# Deck.net
KiCad netlist of a schematic drawn in Altium Designer
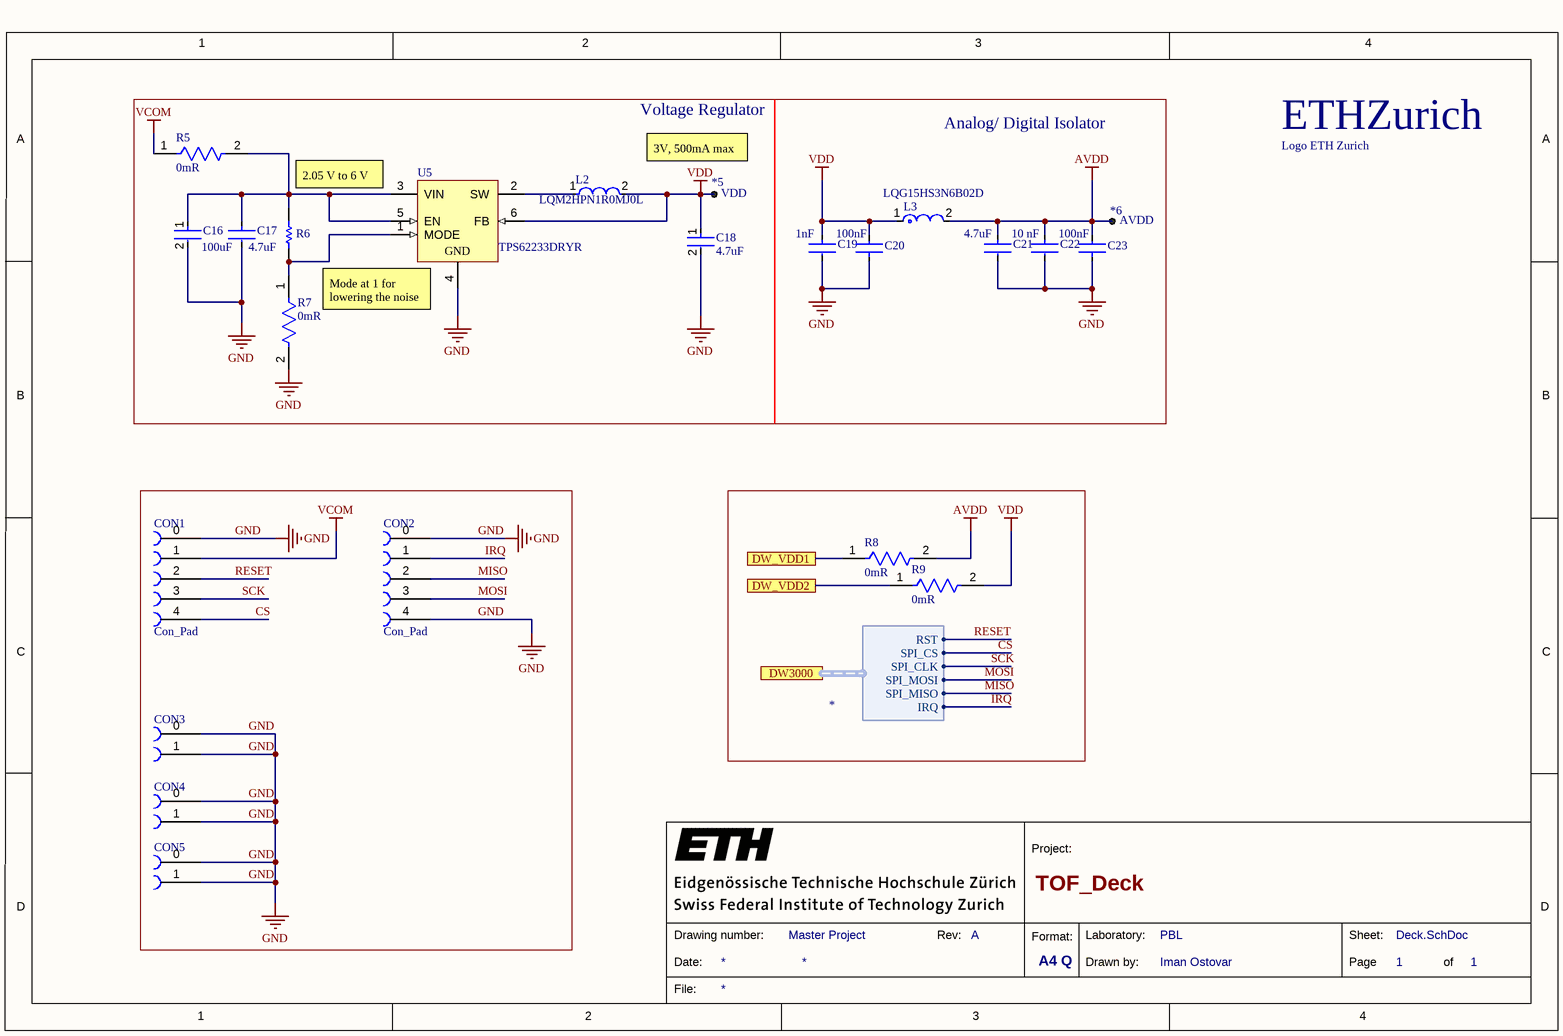
[diagram p0: Deck.SchDoc]

(export (version "E")
  (design (tool "Eeschema 10.0.6"))
  (components
    (comp (ref "*5")
      (value "VDD")
      (footprint "Pad-1mm")
      (description "1mm SMT Test Pad")
      (libsource (lib "ETHZ Vault") (part "Test Pad"))
    )
    (comp (ref "*6")
      (value "AVDD")
      (footprint "Pad-1mm")
      (description "1mm SMT Test Pad")
      (libsource (lib "ETHZ Vault") (part "Test Pad"))
    )
    (comp (ref "A1")
      (value "Logo ETH Zurich")
      (footprint "eth-zurich_3mm")
      (libsource (lib "ETHZ Vault") (part "Logo ETH Zurich"))
    )
    (comp (ref "C16")
      (value "GRM21BR60J107ME15L")
      (footprint "FP-GRM21B-0_2-e0_2_0_7-IPC_A")
      (description "Chip Multilayer Ceramic Capacitors for General Purpose, 0805, 100uF, X5R, 15%, 20%, 6.3V")
      (fields (field (name "TOLERANCE") "20%") (field (name "CAPACITANCE") "100uF"))
      (libsource (lib "Altium Content Vault") (part "b4654b650e69147ec39a6b967a45e02"))
    )
    (comp (ref "C17")
      (value "GRM155R60J475ME47D")
      (footprint "FP-GRM155-0_1-IPC_B")
      (description "Chip Multilayer Ceramic Capacitors for General Purpose, 0402, 4.7uF, X5R, 15%, 20%, 6.3V")
      (fields
        (field (name "VOLTAGE") "6.3V")
        (field (name "CAPACITANCE") "4.7uF")
        (field (name "TOLERANCE") "20%")
      )
      (libsource (lib "") (part "11868f565c42a9108669ba33697ecf6_1"))
    )
    (comp (ref "C18")
      (value "GRM155R60J475ME47D")
      (footprint "FP-GRM155-0_1-IPC_B")
      (description "Chip Multilayer Ceramic Capacitors for General Purpose, 0402, 4.7uF, X5R, 15%, 20%, 6.3V")
      (fields
        (field (name "VOLTAGE") "6.3V")
        (field (name "CAPACITANCE") "4.7uF")
        (field (name "TOLERANCE") "20%")
      )
      (libsource (lib "Altium Content Vault") (part "11868f565c42a9108669ba33697ecf6"))
    )
    (comp (ref "C19")
      (value "GRM1555C1H102JA01D")
      (footprint "FP-GRM155-0_05-IPC_B")
      (description "Chip Multilayer Ceramic Capacitors for General Purpose, 0402, 1000pF, C0G, 30ppm/°C, 5%, 50V")
      (fields
        (field (name "TOLERANCE") "5%")
        (field (name "VOLTAGE") "50V")
        (field (name "CAPACITANCE") "1nF")
      )
      (libsource (lib "Altium Content Vault") (part "02cd4be3c70576c341d710602a673aa"))
    )
    (comp (ref "C20")
      (value "GRM155R71E104ME14D")
      (footprint "FP-GRM155-0_05-IPC_B")
      (description "Chip Multilayer Ceramic Capacitors for General Purpose, 0402, 0.10uF, X7R, 15%, 20%, 25V")
      (fields (field (name "TOLERANCE") "20%") (field (name "CAPACITANCE") "100nF"))
      (libsource (lib "Altium Content Vault") (part "02cd4be3c70576c341d710602a673aa"))
    )
    (comp (ref "C21")
      (value "GRM155R60J475ME47D")
      (footprint "FP-GRM155-0_1-IPC_B")
      (description "Chip Multilayer Ceramic Capacitors for General Purpose, 0402, 4.7uF, X5R, 15%, 20%, 6.3V")
      (fields
        (field (name "VOLTAGE") "6.3V")
        (field (name "CAPACITANCE") "4.7uF")
        (field (name "TOLERANCE") "20%")
      )
      (libsource (lib "") (part "11868f565c42a9108669ba33697ecf6_1"))
    )
    (comp (ref "C22")
      (value "CC0402KRX7R7BB103")
      (footprint "FP-CC0402-MFG")
      (description "CAP CER 10000PF 16V X7R 0402")
      (fields
        (field (name "CAPACITANCE") "10 nF")
        (field (name "TOLERANCE") "0.1")
        (field (name "MANUFACTURER") "YAGEO")
      )
      (libsource (lib "") (part "11868f565c42a9108669ba33697ecf6_1"))
    )
    (comp (ref "C23")
      (value "GRM155R71E104ME14D")
      (footprint "FP-GRM155-0_05-IPC_B")
      (description "Chip Multilayer Ceramic Capacitors for General Purpose, 0402, 0.10uF, X7R, 15%, 20%, 25V")
      (fields (field (name "TOLERANCE") "20%") (field (name "CAPACITANCE") "100nF"))
      (libsource (lib "Altium Content Vault") (part "02cd4be3c70576c341d710602a673aa"))
    )
    (comp (ref "CON1")
      (value "Con_Pad")
      (footprint "PcbLib2:Cons_Pad")
      (libsource (lib "Schlib2") (part "Con_Pad"))
    )
    (comp (ref "CON2")
      (value "Con_Pad")
      (footprint "PcbLib2:Cons_Pad")
      (libsource (lib "Schlib2") (part "Con_Pad"))
    )
    (comp (ref "CON3")
      (value "Con_Pad_GND")
      (footprint "PcbLib3:PCBComponent_1")
      (libsource (lib "Schlib3") (part "Con_Pad_GND"))
    )
    (comp (ref "CON4")
      (value "Con_Pad_GND")
      (footprint "PcbLib3:PCBComponent_1")
      (libsource (lib "Schlib3") (part "Con_Pad_GND"))
    )
    (comp (ref "CON5")
      (value "Con_Pad_GND")
      (footprint "PcbLib3:PCBComponent_1")
      (libsource (lib "Schlib3") (part "Con_Pad_GND"))
    )
    (comp (ref "L2")
      (value "LQM2HPN1R0MJ0L")
      (footprint "FP-LQM2HPN_J0-IPC_B")
      (description "FIXED IND 1UH 1.5A 90 MOHM SMD")
      (fields (field (name "TOLERANCE") "20%"))
      (libsource (lib "Altium Content Vault") (part "725321dda6339637d4d059423bc1c3c"))
    )
    (comp (ref "L3")
      (value "LQG15HS3N6B02D")
      (footprint "FP-LQG15HH_02-IPC_A")
      (description "Multilayer type RF Inductor 3.6nH ±0.1nH 0.14Ω 750mA 0402")
      (libsource (lib "Altium Content Vault") (part "4cc4b267dca4c8e51f7102f422741d8"))
    )
    (comp (ref "R5")
      (value "CRCW04020000Z0ED")
      (footprint "FP-CRCW0402-e3-IPC_C")
      (description "RES Thick Film, 0Ω, 0.063W, 0402")
      (fields (field (name "TOLERANCE") "5%") (field (name "RESISTANCE") "0mR"))
      (libsource (lib "Altium Content Vault") (part "1029c3af85768c4190bb7ad29bc67b5"))
    )
    (comp (ref "R6")
      (value "CPF0402B47K5E1")
      (footprint "RESC1005X35X20LL05T10")
      (description "47.5k, CPF0402B47K5E1")
      (fields (field (name "MANUFACTURER") "TE Connectivity / AMP"))
      (libsource (lib "Altium Content Vault") (part "RES"))
    )
    (comp (ref "R7")
      (value "CRCW04020000Z0ED")
      (footprint "FP-CRCW0402-e3-IPC_C")
      (description "RES Thick Film, 0Ω, 0.063W, 0402")
      (fields (field (name "TOLERANCE") "5%") (field (name "RESISTANCE") "0mR"))
      (libsource (lib "Altium Content Vault") (part "1029c3af85768c4190bb7ad29bc67b5"))
    )
    (comp (ref "R8")
      (value "CRCW04020000Z0ED")
      (footprint "FP-CRCW0402-e3-IPC_C")
      (description "RES Thick Film, 0Ω, 0.063W, 0402")
      (fields (field (name "TOLERANCE") "5%") (field (name "RESISTANCE") "0mR"))
      (libsource (lib "Altium Content Vault") (part "1029c3af85768c4190bb7ad29bc67b5"))
    )
    (comp (ref "R9")
      (value "CRCW04020000Z0ED")
      (footprint "FP-CRCW0402-e3-IPC_C")
      (description "RES Thick Film, 0Ω, 0.063W, 0402")
      (fields (field (name "TOLERANCE") "5%") (field (name "RESISTANCE") "0mR"))
      (libsource (lib "Altium Content Vault") (part "1029c3af85768c4190bb7ad29bc67b5"))
    )
    (comp (ref "U5")
      (value "TPS62233DRYR")
      (footprint "DRY0006A")
      (fields (field (name "MANUFACTURER") "Texas Instruments"))
      (libsource (lib "Altium Content Vault") (part "TI-TPS62233DRY6"))
    )
  )
  (nets
    (net (code "2") (name "/CS") (class "Default")
      (node (ref "CON1") (pin "4") (pinfunction "4_4") (pintype "passive"))
    )
    (net (code "3") (name "/DW_VDD1") (class "Default")
      (node (ref "R8") (pin "1") (pinfunction "1_1") (pintype "passive"))
    )
    (net (code "4") (name "/DW_VDD2") (class "Default")
      (node (ref "R9") (pin "1") (pinfunction "1_1") (pintype "passive"))
    )
    (net (code "5") (name "/IRQ") (class "Default")
      (node (ref "CON2") (pin "1") (pinfunction "1_1") (pintype "passive"))
    )
    (net (code "6") (name "/MISO") (class "Default")
      (node (ref "CON2") (pin "2") (pinfunction "2_2") (pintype "passive"))
    )
    (net (code "7") (name "/MOSI") (class "Default")
      (node (ref "CON2") (pin "3") (pinfunction "3_3") (pintype "passive"))
    )
    (net (code "8") (name "/RESET") (class "Default")
      (node (ref "CON1") (pin "2") (pinfunction "2_2") (pintype "passive"))
    )
    (net (code "9") (name "/SCK") (class "Default")
      (node (ref "CON1") (pin "3") (pinfunction "3_3") (pintype "passive"))
    )
    (net (code "11") (name "AVDD") (class "Default")
      (node (ref "*6") (pin "1") (pinfunction "1_1") (pintype "passive"))
      (node (ref "C21") (pin "1") (pinfunction "1_1") (pintype "passive"))
      (node (ref "C22") (pin "1") (pinfunction "1_1") (pintype "passive"))
      (node (ref "C23") (pin "2") (pinfunction "2_2") (pintype "passive"))
      (node (ref "L3") (pin "2") (pinfunction "2_2") (pintype "passive"))
      (node (ref "R8") (pin "2") (pinfunction "2_2") (pintype "passive"))
    )
    (net (code "12") (name "GND") (class "Default")
      (node (ref "C16") (pin "2") (pinfunction "2_2") (pintype "passive"))
      (node (ref "C17") (pin "2") (pinfunction "2_2") (pintype "passive"))
      (node (ref "C18") (pin "2") (pinfunction "2_2") (pintype "passive"))
      (node (ref "C19") (pin "2") (pinfunction "2_2") (pintype "passive"))
      (node (ref "C20") (pin "1") (pinfunction "1_1") (pintype "passive"))
      (node (ref "C21") (pin "2") (pinfunction "2_2") (pintype "passive"))
      (node (ref "C22") (pin "2") (pinfunction "2_2") (pintype "passive"))
      (node (ref "C23") (pin "1") (pinfunction "1_1") (pintype "passive"))
      (node (ref "CON1") (pin "0") (pinfunction "0_0") (pintype "passive"))
      (node (ref "CON2") (pin "0") (pinfunction "0_0") (pintype "passive"))
      (node (ref "CON2") (pin "4") (pinfunction "4_4") (pintype "passive"))
      (node (ref "CON3") (pin "0") (pinfunction "0_0") (pintype "passive"))
      (node (ref "CON3") (pin "1") (pinfunction "1_1") (pintype "passive"))
      (node (ref "CON4") (pin "0") (pinfunction "0_0") (pintype "passive"))
      (node (ref "CON4") (pin "1") (pinfunction "1_1") (pintype "passive"))
      (node (ref "CON5") (pin "0") (pinfunction "0_0") (pintype "passive"))
      (node (ref "CON5") (pin "1") (pinfunction "1_1") (pintype "passive"))
      (node (ref "R7") (pin "2") (pinfunction "2_2") (pintype "passive"))
      (node (ref "U5") (pin "4") (pinfunction "GND_4") (pintype "power_in"))
    )
    (net (code "13") (name "Net-(U5-EN)") (class "Default")
      (node (ref "C16") (pin "1") (pinfunction "1_1") (pintype "passive"))
      (node (ref "C17") (pin "1") (pinfunction "1_1") (pintype "passive"))
      (node (ref "R5") (pin "2") (pinfunction "2_2") (pintype "passive"))
      (node (ref "R6") (pin "2") (pinfunction "2_2") (pintype "passive"))
      (node (ref "U5") (pin "3") (pinfunction "VIN_3") (pintype "power_in"))
      (node (ref "U5") (pin "5") (pinfunction "EN_5") (pintype "input"))
    )
    (net (code "14") (name "Net-(U5-MODE)") (class "Default")
      (node (ref "R6") (pin "1") (pinfunction "1_1") (pintype "passive"))
      (node (ref "R7") (pin "1") (pinfunction "1_1") (pintype "passive"))
      (node (ref "U5") (pin "1") (pinfunction "MODE_1") (pintype "input"))
    )
    (net (code "15") (name "Net-(U5-SW)") (class "Default")
      (node (ref "L2") (pin "1") (pinfunction "1_1") (pintype "passive"))
      (node (ref "U5") (pin "2") (pinfunction "SW_2") (pintype "power_in"))
    )
    (net (code "16") (name "VCOM") (class "Default")
      (node (ref "CON1") (pin "1") (pinfunction "1_1") (pintype "passive"))
      (node (ref "R5") (pin "1") (pinfunction "1_1") (pintype "passive"))
    )
    (net (code "17") (name "VDD") (class "Default")
      (node (ref "*5") (pin "1") (pinfunction "1_1") (pintype "passive"))
      (node (ref "C18") (pin "1") (pinfunction "1_1") (pintype "passive"))
      (node (ref "C19") (pin "1") (pinfunction "1_1") (pintype "passive"))
      (node (ref "C20") (pin "2") (pinfunction "2_2") (pintype "passive"))
      (node (ref "L2") (pin "2") (pinfunction "2_2") (pintype "passive"))
      (node (ref "L3") (pin "1") (pinfunction "1_1") (pintype "passive"))
      (node (ref "R9") (pin "2") (pinfunction "2_2") (pintype "passive"))
      (node (ref "U5") (pin "6") (pinfunction "FB_6") (pintype "input"))
    )
  )
)
